# ChimesV1.net
KiCad netlist of a schematic drawn in EAGLE
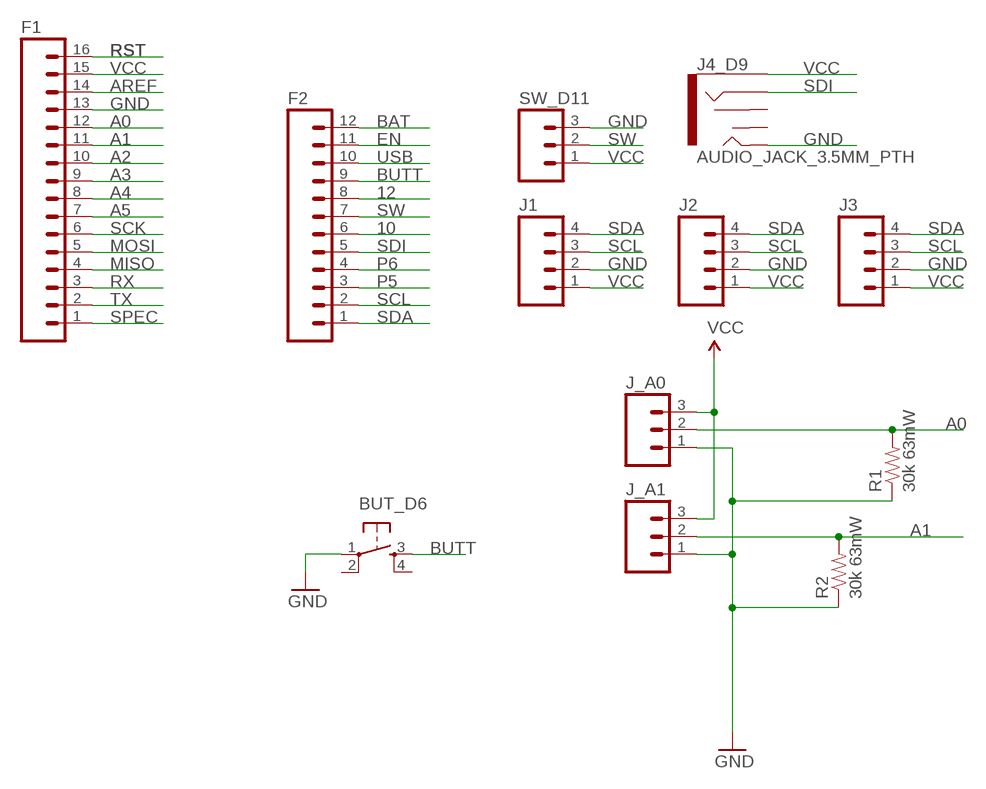
[diagram p0: schematic, sheet 1]

(export (version "E")
  (design (tool "Eeschema 10.0.6"))
  (components
    (comp (ref "BUT_D6")
      (value "TAC_SWITCHPTH")
      (footprint "eagle-import:TACTILE-PTH")
      (libsource (lib "eagle-import") (part "TAC_SWITCHPTH"))
    )
    (comp (ref "F1")
      (value "M16PTH")
      (footprint "eagle-import:1X16")
      (libsource (lib "eagle-import") (part "M16PTH"))
    )
    (comp (ref "F2")
      (value "M12PTH")
      (footprint "eagle-import:1X12")
      (libsource (lib "eagle-import") (part "M12PTH"))
    )
    (comp (ref "J1")
      (value "M04PTH")
      (footprint "eagle-import:1X04")
      (libsource (lib "eagle-import") (part "M04PTH"))
    )
    (comp (ref "J2")
      (value "M04PTH")
      (footprint "eagle-import:1X04")
      (libsource (lib "eagle-import") (part "M04PTH"))
    )
    (comp (ref "J3")
      (value "M04PTH")
      (footprint "eagle-import:1X04")
      (libsource (lib "eagle-import") (part "M04PTH"))
    )
    (comp (ref "J4_D9")
      (value "AUDIO_JACK_3.5MM_PTH")
      (footprint "eagle-import:AUDIO-JACK")
      (libsource (lib "eagle-import") (part "AUDIO_JACK_3.5MM_PTH"))
    )
    (comp (ref "J_A0")
      (value "M03JST-PTH-VERT")
      (footprint "eagle-import:JST-3-PTH-VERT")
      (libsource (lib "eagle-import") (part "M03JST-PTH-VERT"))
    )
    (comp (ref "J_A1")
      (value "M03JST-PTH-VERT")
      (footprint "eagle-import:JST-3-PTH-VERT")
      (libsource (lib "eagle-import") (part "M03JST-PTH-VERT"))
    )
    (comp (ref "R1")
      (value "30k 63mW")
      (footprint "eagle-import:1206")
      (libsource (lib "eagle-import") (part "RESISTOR1206"))
    )
    (comp (ref "R2")
      (value "30k 63mW")
      (footprint "eagle-import:1206")
      (libsource (lib "eagle-import") (part "RESISTOR1206"))
    )
    (comp (ref "SW_D11")
      (value "M03PTH")
      (footprint "eagle-import:1X03")
      (libsource (lib "eagle-import") (part "M03PTH"))
    )
  )
  (nets
    (net (code "1") (name "/10") (class "Default")
      (node (ref "F2") (pin "6") (pinfunction "6_6") (pintype "passive"))
    )
    (net (code "2") (name "/12") (class "Default")
      (node (ref "F2") (pin "8") (pinfunction "8_8") (pintype "passive"))
    )
    (net (code "3") (name "/A0") (class "Default")
      (node (ref "F1") (pin "12") (pinfunction "12_12") (pintype "passive"))
      (node (ref "J_A0") (pin "2") (pinfunction "2_2") (pintype "passive"))
      (node (ref "R1") (pin "2") (pinfunction "2_2") (pintype "passive"))
    )
    (net (code "4") (name "/A1") (class "Default")
      (node (ref "F1") (pin "11") (pinfunction "11_11") (pintype "passive"))
      (node (ref "J_A1") (pin "2") (pinfunction "2_2") (pintype "passive"))
      (node (ref "R2") (pin "2") (pinfunction "2_2") (pintype "passive"))
    )
    (net (code "5") (name "/A2") (class "Default")
      (node (ref "F1") (pin "10") (pinfunction "10_10") (pintype "passive"))
    )
    (net (code "6") (name "/A3") (class "Default")
      (node (ref "F1") (pin "9") (pinfunction "9_9") (pintype "passive"))
    )
    (net (code "7") (name "/A4") (class "Default")
      (node (ref "F1") (pin "8") (pinfunction "8_8") (pintype "passive"))
    )
    (net (code "8") (name "/A5") (class "Default")
      (node (ref "F1") (pin "7") (pinfunction "7_7") (pintype "passive"))
    )
    (net (code "9") (name "/AREF") (class "Default")
      (node (ref "F1") (pin "14") (pinfunction "14_14") (pintype "passive"))
    )
    (net (code "10") (name "/BAT") (class "Default")
      (node (ref "F2") (pin "12") (pinfunction "12_12") (pintype "passive"))
    )
    (net (code "11") (name "/BUTT") (class "Default")
      (node (ref "BUT_D6") (pin "3") (pinfunction "3_3") (pintype "passive"))
      (node (ref "F2") (pin "9") (pinfunction "9_9") (pintype "passive"))
    )
    (net (code "12") (name "/EN") (class "Default")
      (node (ref "F2") (pin "11") (pinfunction "11_11") (pintype "passive"))
    )
    (net (code "13") (name "/MISO") (class "Default")
      (node (ref "F1") (pin "4") (pinfunction "4_4") (pintype "passive"))
    )
    (net (code "14") (name "/MOSI") (class "Default")
      (node (ref "F1") (pin "5") (pinfunction "5_5") (pintype "passive"))
    )
    (net (code "15") (name "/P5") (class "Default")
      (node (ref "F2") (pin "3") (pinfunction "3_3") (pintype "passive"))
    )
    (net (code "16") (name "/P6") (class "Default")
      (node (ref "F2") (pin "4") (pinfunction "4_4") (pintype "passive"))
    )
    (net (code "17") (name "/RST") (class "Default")
      (node (ref "F1") (pin "16") (pinfunction "16_16") (pintype "passive"))
    )
    (net (code "18") (name "/RX") (class "Default")
      (node (ref "F1") (pin "3") (pinfunction "3_3") (pintype "passive"))
    )
    (net (code "19") (name "/SCK") (class "Default")
      (node (ref "F1") (pin "6") (pinfunction "6_6") (pintype "passive"))
    )
    (net (code "20") (name "/SCL") (class "Default")
      (node (ref "F2") (pin "2") (pinfunction "2_2") (pintype "passive"))
      (node (ref "J1") (pin "3") (pinfunction "3_3") (pintype "passive"))
      (node (ref "J2") (pin "3") (pinfunction "3_3") (pintype "passive"))
      (node (ref "J3") (pin "3") (pinfunction "3_3") (pintype "passive"))
    )
    (net (code "21") (name "/SDA") (class "Default")
      (node (ref "F2") (pin "1") (pinfunction "1_1") (pintype "passive"))
      (node (ref "J1") (pin "4") (pinfunction "4_4") (pintype "passive"))
      (node (ref "J2") (pin "4") (pinfunction "4_4") (pintype "passive"))
      (node (ref "J3") (pin "4") (pinfunction "4_4") (pintype "passive"))
    )
    (net (code "22") (name "/SDI") (class "Default")
      (node (ref "F2") (pin "5") (pinfunction "5_5") (pintype "passive"))
      (node (ref "J4_D9") (pin "RING") (pinfunction "RING_RING") (pintype "bidirectional"))
    )
    (net (code "23") (name "/SPEC") (class "Default")
      (node (ref "F1") (pin "1") (pinfunction "1_1") (pintype "passive"))
    )
    (net (code "24") (name "/SW") (class "Default")
      (node (ref "F2") (pin "7") (pinfunction "7_7") (pintype "passive"))
      (node (ref "SW_D11") (pin "2") (pinfunction "2_2") (pintype "passive"))
    )
    (net (code "25") (name "/TX") (class "Default")
      (node (ref "F1") (pin "2") (pinfunction "2_2") (pintype "passive"))
    )
    (net (code "26") (name "/USB") (class "Default")
      (node (ref "F2") (pin "10") (pinfunction "10_10") (pintype "passive"))
    )
    (net (code "27") (name "GND") (class "Default")
      (node (ref "BUT_D6") (pin "1") (pinfunction "1_1") (pintype "passive"))
      (node (ref "F1") (pin "13") (pinfunction "13_13") (pintype "passive"))
      (node (ref "J1") (pin "2") (pinfunction "2_2") (pintype "passive"))
      (node (ref "J2") (pin "2") (pinfunction "2_2") (pintype "passive"))
      (node (ref "J3") (pin "2") (pinfunction "2_2") (pintype "passive"))
      (node (ref "J4_D9") (pin "TIP") (pinfunction "TIP_TIP") (pintype "bidirectional"))
      (node (ref "J_A0") (pin "1") (pinfunction "1_1") (pintype "passive"))
      (node (ref "J_A1") (pin "1") (pinfunction "1_1") (pintype "passive"))
      (node (ref "R1") (pin "1") (pinfunction "1_1") (pintype "passive"))
      (node (ref "R2") (pin "1") (pinfunction "1_1") (pintype "passive"))
      (node (ref "SW_D11") (pin "3") (pinfunction "3_3") (pintype "passive"))
    )
    (net (code "28") (name "VCC") (class "Default")
      (node (ref "F1") (pin "15") (pinfunction "15_15") (pintype "passive"))
      (node (ref "J1") (pin "1") (pinfunction "1_1") (pintype "passive"))
      (node (ref "J2") (pin "1") (pinfunction "1_1") (pintype "passive"))
      (node (ref "J3") (pin "1") (pinfunction "1_1") (pintype "passive"))
      (node (ref "J4_D9") (pin "SLEEVE") (pinfunction "SLEEVE_SLEEVE") (pintype "bidirectional"))
      (node (ref "J_A0") (pin "3") (pinfunction "3_3") (pintype "passive"))
      (node (ref "J_A1") (pin "3") (pinfunction "3_3") (pintype "passive"))
      (node (ref "SW_D11") (pin "1") (pinfunction "1_1") (pintype "passive"))
    )
    (net (code "29") (name "unconnected-(BUT_D6-Pad2)") (class "Default")
      (node (ref "BUT_D6") (pin "2") (pinfunction "2_2") (pintype "passive"))
    )
    (net (code "30") (name "unconnected-(BUT_D6-Pad4)") (class "Default")
      (node (ref "BUT_D6") (pin "4") (pinfunction "4_4") (pintype "passive"))
    )
    (net (code "31") (name "unconnected-(J4_D9-PadRSH)") (class "Default")
      (node (ref "J4_D9") (pin "RSH") (pinfunction "RSH_RSH") (pintype "bidirectional"))
    )
    (net (code "32") (name "unconnected-(J4_D9-PadTSH)") (class "Default")
      (node (ref "J4_D9") (pin "TSH") (pinfunction "TSH_TSH") (pintype "bidirectional"))
    )
  )
)
